# POWER.net
KiCad netlist of a schematic drawn in Altium Designer
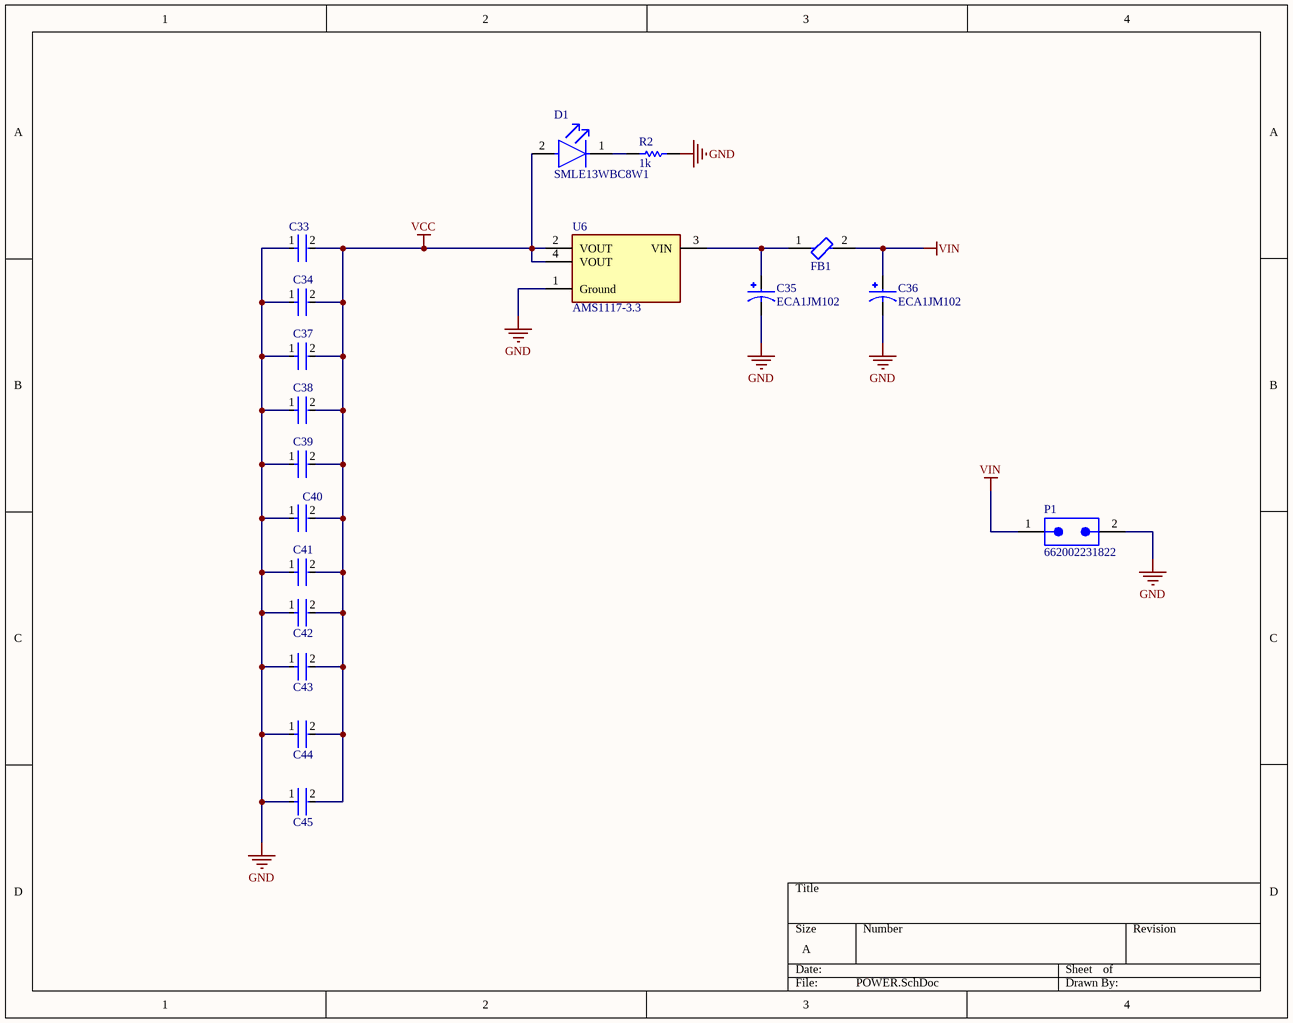
[diagram p0: POWER.SchDoc]

(export (version "E")
  (design (tool "Eeschema 10.0.6"))
  (components
    (comp (ref "C33")
      (value "C0603X6S0G474M030BC")
      (footprint "FP-C0603-030-0_03-MFG")
      (description "Multilayer Ceramic Capacitors 470nF ±20% 4V X6S SMD 0201")
      (fields (field (name "TOLERANCE") "20%"))
      (libsource (lib "Altium Content Vault") (part "02cd4be3c70576c341d710602a673aa"))
    )
    (comp (ref "C34")
      (value "C0603X6S0G474M030BC")
      (footprint "FP-C0603-030-0_03-MFG")
      (description "Multilayer Ceramic Capacitors 470nF ±20% 4V X6S SMD 0201")
      (fields (field (name "TOLERANCE") "20%"))
      (libsource (lib "Altium Content Vault") (part "02cd4be3c70576c341d710602a673aa"))
    )
    (comp (ref "C35")
      (value "ECA1JM102")
      (footprint "CAPPRD750W80D1600H2500")
      (description "1000ÂµF 63V Aluminum Electrolytic Capacitors Radial, Can 2000 Hrs @ 85Â°C")
      (fields (field (name "MF") "Panasonic"))
      (libsource (lib "ECA1JM102") (part "ECA1JM102"))
    )
    (comp (ref "C36")
      (value "ECA1JM102")
      (footprint "CAPPRD750W80D1600H2500")
      (description "1000ÂµF 63V Aluminum Electrolytic Capacitors Radial, Can 2000 Hrs @ 85Â°C")
      (fields (field (name "MF") "Panasonic"))
      (libsource (lib "ECA1JM102") (part "ECA1JM102"))
    )
    (comp (ref "C37")
      (value "C0603X6S0G474M030BC")
      (footprint "FP-C0603-030-0_03-MFG")
      (description "Multilayer Ceramic Capacitors 470nF ±20% 4V X6S SMD 0201")
      (fields (field (name "TOLERANCE") "20%"))
      (libsource (lib "Altium Content Vault") (part "02cd4be3c70576c341d710602a673aa"))
    )
    (comp (ref "C38")
      (value "C0603X6S0G474M030BC")
      (footprint "FP-C0603-030-0_03-MFG")
      (description "Multilayer Ceramic Capacitors 470nF ±20% 4V X6S SMD 0201")
      (fields (field (name "TOLERANCE") "20%"))
      (libsource (lib "Altium Content Vault") (part "02cd4be3c70576c341d710602a673aa"))
    )
    (comp (ref "C39")
      (value "C0603X6S0G474M030BC")
      (footprint "FP-C0603-030-0_03-MFG")
      (description "Multilayer Ceramic Capacitors 470nF ±20% 4V X6S SMD 0201")
      (fields (field (name "TOLERANCE") "20%"))
      (libsource (lib "Altium Content Vault") (part "02cd4be3c70576c341d710602a673aa"))
    )
    (comp (ref "C40")
      (value "C0603X6S0G474M030BC")
      (footprint "FP-C0603-030-0_03-MFG")
      (description "Multilayer Ceramic Capacitors 470nF ±20% 4V X6S SMD 0201")
      (fields (field (name "TOLERANCE") "20%"))
      (libsource (lib "Altium Content Vault") (part "02cd4be3c70576c341d710602a673aa"))
    )
    (comp (ref "C41")
      (value "C0603X6S0G474M030BC")
      (footprint "FP-C0603-030-0_03-MFG")
      (description "Multilayer Ceramic Capacitors 470nF ±20% 4V X6S SMD 0201")
      (fields (field (name "TOLERANCE") "20%"))
      (libsource (lib "Altium Content Vault") (part "02cd4be3c70576c341d710602a673aa"))
    )
    (comp (ref "C42")
      (value "C0603X6S0G474M030BC")
      (footprint "FP-C0603-030-0_03-MFG")
      (description "Multilayer Ceramic Capacitors 470nF ±20% 4V X6S SMD 0201")
      (fields (field (name "TOLERANCE") "20%"))
      (libsource (lib "Altium Content Vault") (part "02cd4be3c70576c341d710602a673aa"))
    )
    (comp (ref "C43")
      (value "C0603X6S0G474M030BC")
      (footprint "FP-C0603-030-0_03-MFG")
      (description "Multilayer Ceramic Capacitors 470nF ±20% 4V X6S SMD 0201")
      (fields (field (name "TOLERANCE") "20%"))
      (libsource (lib "Altium Content Vault") (part "02cd4be3c70576c341d710602a673aa"))
    )
    (comp (ref "C44")
      (value "C0603X6S0G474M030BC")
      (footprint "FP-C0603-030-0_03-MFG")
      (description "Multilayer Ceramic Capacitors 470nF ±20% 4V X6S SMD 0201")
      (fields (field (name "TOLERANCE") "20%"))
      (libsource (lib "Altium Content Vault") (part "02cd4be3c70576c341d710602a673aa"))
    )
    (comp (ref "C45")
      (value "C0603X6S0G474M030BC")
      (footprint "FP-C0603-030-0_03-MFG")
      (description "Multilayer Ceramic Capacitors 470nF ±20% 4V X6S SMD 0201")
      (fields (field (name "TOLERANCE") "20%"))
      (libsource (lib "Altium Content Vault") (part "02cd4be3c70576c341d710602a673aa"))
    )
    (comp (ref "D1")
      (value "SMLE13WBC8W1")
      (footprint "FP-SMLE13WBC8W1-MFG")
      (description "LED WHITE 0603 SMD")
      (fields
        (field (name "OCTOPART") "https://octopart.com/smle13wbc8w1-rohm-22224565")
        (field (name "MANUFACTURER") "Rohm")
      )
      (libsource (lib "Altium Content Vault") (part "8706943c75ba83719d021d2fdc84c58"))
    )
    (comp (ref "FB1")
      (value "BLM18KG121TN1D")
      (footprint "FP-BLM18-0_15-t0_6-d1_2-IPC_A")
      (description "FERRITE BEAD 120 OHM 0603 1LN")
      (fields (field (name "TOLERANCE") "25%"))
      (libsource (lib "Altium Content Vault") (part "5f30dd21d616792df468990f7003faa"))
    )
    (comp (ref "P1")
      (value "662002231822")
      (footprint "662002231822")
      (libsource (lib "Altium Content Vault") (part "Header_Male_2R_02P(A)"))
    )
    (comp (ref "R2")
      (value "1k")
      (footprint "RESC2013X60X35ML10T20")
      (fields (field (name "TOLERANCE") "5%") (field (name "MANUFACTURER") "Yageo"))
      (libsource (lib "Altium Content Vault") (part "RES-2"))
    )
    (comp (ref "U6")
      (value "AMS1117-3.3")
      (footprint "FP-AMS1117-IPC_C")
      (description "LDO Voltage Regulators 1A, 3.3V")
      (fields
        (field (name "OCTOPART") "https://octopart.com/ams1117-3.3-advanced+monolithic+systems-25899300")
        (field (name "MANUFACTURER") "Advanced Monolithic Systems")
      )
      (libsource (lib "Altium Content Vault") (part "8bdbb5f8e77002000e30dd2845d0354"))
    )
  )
  (nets
    (net (code "1") (name "GND") (class "Default")
      (node (ref "C33") (pin "1") (pinfunction "1_1") (pintype "passive"))
      (node (ref "C34") (pin "1") (pinfunction "1_1") (pintype "passive"))
      (node (ref "C35") (pin "N") (pinfunction "N_N") (pintype "passive"))
      (node (ref "C36") (pin "N") (pinfunction "N_N") (pintype "passive"))
      (node (ref "C37") (pin "1") (pinfunction "1_1") (pintype "passive"))
      (node (ref "C38") (pin "1") (pinfunction "1_1") (pintype "passive"))
      (node (ref "C39") (pin "1") (pinfunction "1_1") (pintype "passive"))
      (node (ref "C40") (pin "1") (pinfunction "1_1") (pintype "passive"))
      (node (ref "C41") (pin "1") (pinfunction "1_1") (pintype "passive"))
      (node (ref "C42") (pin "1") (pinfunction "1_1") (pintype "passive"))
      (node (ref "C43") (pin "1") (pinfunction "1_1") (pintype "passive"))
      (node (ref "C44") (pin "1") (pinfunction "1_1") (pintype "passive"))
      (node (ref "C45") (pin "1") (pinfunction "1_1") (pintype "passive"))
      (node (ref "P1") (pin "2") (pinfunction "2_2") (pintype "passive"))
      (node (ref "R2") (pin "1") (pinfunction "1_1") (pintype "passive"))
      (node (ref "U6") (pin "1") (pinfunction "Ground_1") (pintype "power_in"))
    )
    (net (code "2") (name "Net-(D1-C)") (class "Default")
      (node (ref "D1") (pin "1") (pinfunction "C_1") (pintype "passive"))
      (node (ref "R2") (pin "2") (pinfunction "2_2") (pintype "passive"))
    )
    (net (code "3") (name "Net-(U6-VIN)") (class "Default")
      (node (ref "C35") (pin "P") (pinfunction "P_P") (pintype "passive"))
      (node (ref "FB1") (pin "1") (pinfunction "1_1") (pintype "passive"))
      (node (ref "U6") (pin "3") (pinfunction "VIN_3") (pintype "power_in"))
    )
    (net (code "4") (name "VCC") (class "Default")
      (node (ref "C33") (pin "2") (pinfunction "2_2") (pintype "passive"))
      (node (ref "C34") (pin "2") (pinfunction "2_2") (pintype "passive"))
      (node (ref "C37") (pin "2") (pinfunction "2_2") (pintype "passive"))
      (node (ref "C38") (pin "2") (pinfunction "2_2") (pintype "passive"))
      (node (ref "C39") (pin "2") (pinfunction "2_2") (pintype "passive"))
      (node (ref "C40") (pin "2") (pinfunction "2_2") (pintype "passive"))
      (node (ref "C41") (pin "2") (pinfunction "2_2") (pintype "passive"))
      (node (ref "C42") (pin "2") (pinfunction "2_2") (pintype "passive"))
      (node (ref "C43") (pin "2") (pinfunction "2_2") (pintype "passive"))
      (node (ref "C44") (pin "2") (pinfunction "2_2") (pintype "passive"))
      (node (ref "C45") (pin "2") (pinfunction "2_2") (pintype "passive"))
      (node (ref "D1") (pin "2") (pinfunction "A_2") (pintype "passive"))
      (node (ref "U6") (pin "2") (pinfunction "VOUT_2") (pintype "passive"))
      (node (ref "U6") (pin "4") (pinfunction "VOUT_4") (pintype "passive"))
    )
    (net (code "5") (name "VIN") (class "Default")
      (node (ref "C36") (pin "P") (pinfunction "P_P") (pintype "passive"))
      (node (ref "FB1") (pin "2") (pinfunction "2_2") (pintype "passive"))
      (node (ref "P1") (pin "1") (pinfunction "1_1") (pintype "passive"))
    )
  )
)
